# GPIOPins.net
KiCad netlist of a schematic drawn in Altium Designer
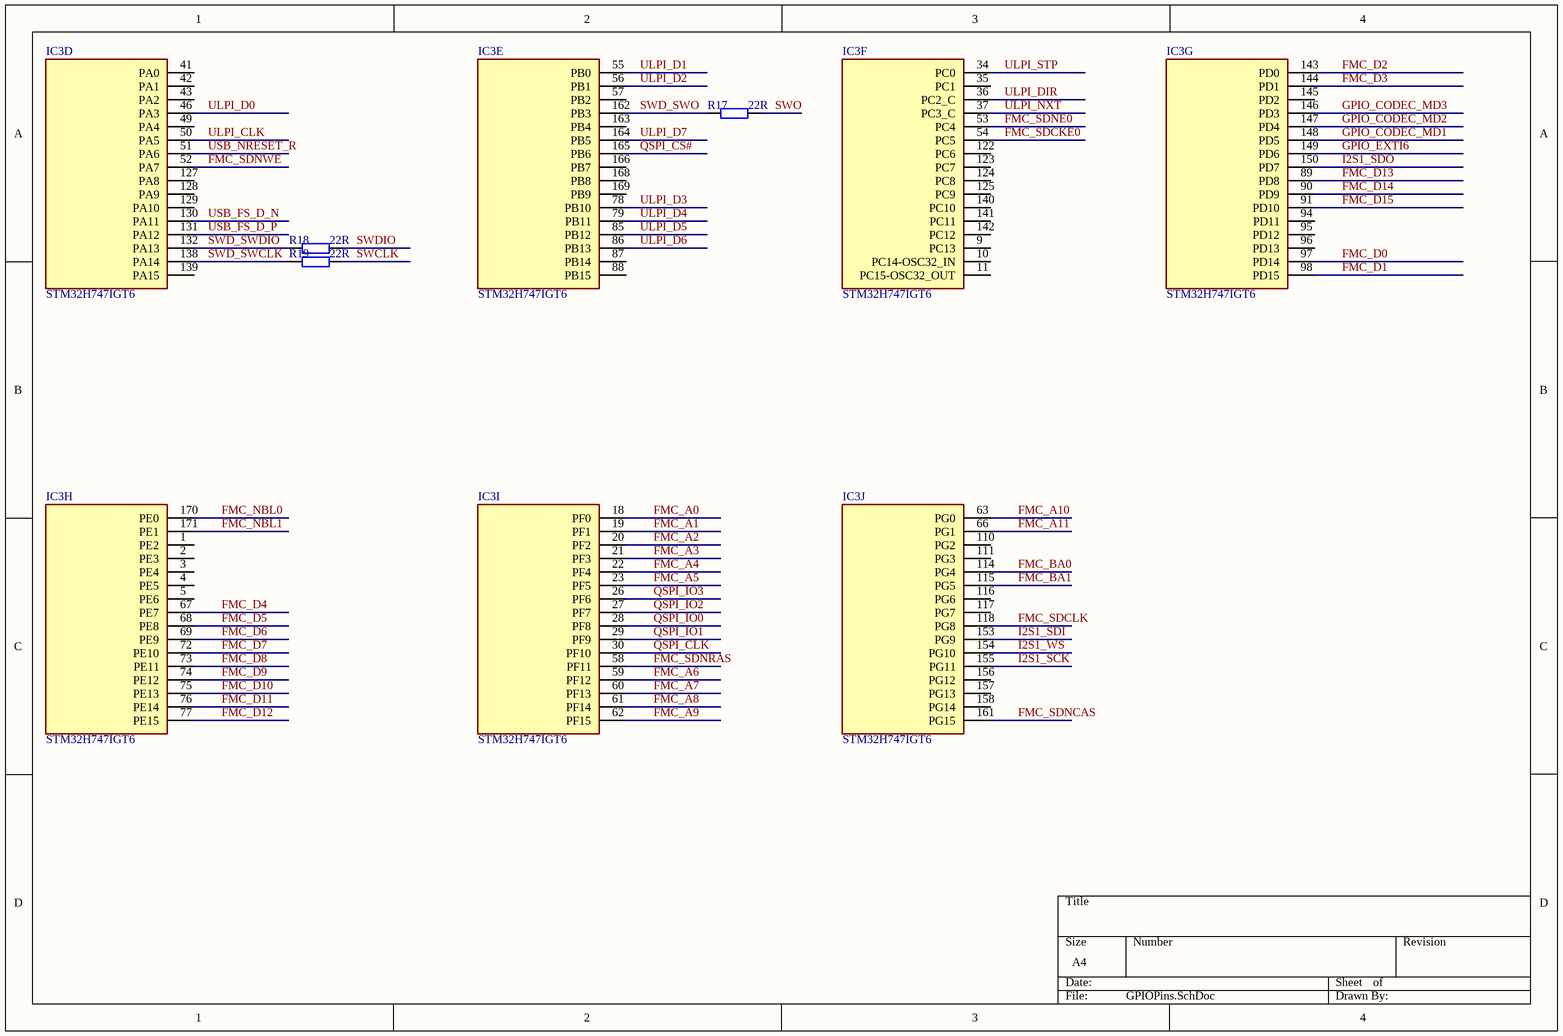
[diagram p0: GPIOPins.SchDoc]

(export (version "E")
  (design (tool "Eeschema 10.0.6"))
  (components
    (comp (ref "IC3")
      (value "STM32H747IGT6")
      (footprint "Footprint-Lib-PhilsLab:QFP50P2600X2600X160-176N")
      (description "Integrated Circuit")
      (fields (field (name "MOUSER PART NUMBER") "511-STM32H747IGT6"))
      (libsource (lib "Schematic-Lib-PhilsLab") (part "STM32H747IGT6"))
    )
    (comp (ref "R17")
      (value "22R")
      (footprint "RES_0402")
      (description "Resistor SMD 0402")
      (libsource (lib "Schematic-Lib-PhilsLab") (part "RES_0402"))
    )
    (comp (ref "R18")
      (value "22R")
      (footprint "RES_0402")
      (description "Resistor SMD 0402")
      (libsource (lib "Schematic-Lib-PhilsLab") (part "RES_0402"))
    )
    (comp (ref "R19")
      (value "22R")
      (footprint "RES_0402")
      (description "Resistor SMD 0402")
      (libsource (lib "Schematic-Lib-PhilsLab") (part "RES_0402"))
    )
  )
  (nets
    (net (code "1") (name "/FMC_A0") (class "Default")
      (node (ref "IC3") (pin "18") (pinfunction "PF0_18") (pintype "passive"))
    )
    (net (code "2") (name "/FMC_A1") (class "Default")
      (node (ref "IC3") (pin "19") (pinfunction "PF1_19") (pintype "passive"))
    )
    (net (code "3") (name "/FMC_A2") (class "Default")
      (node (ref "IC3") (pin "20") (pinfunction "PF2_20") (pintype "passive"))
    )
    (net (code "4") (name "/FMC_A3") (class "Default")
      (node (ref "IC3") (pin "21") (pinfunction "PF3_21") (pintype "passive"))
    )
    (net (code "5") (name "/FMC_A4") (class "Default")
      (node (ref "IC3") (pin "22") (pinfunction "PF4_22") (pintype "passive"))
    )
    (net (code "6") (name "/FMC_A5") (class "Default")
      (node (ref "IC3") (pin "23") (pinfunction "PF5_23") (pintype "passive"))
    )
    (net (code "7") (name "/FMC_A6") (class "Default")
      (node (ref "IC3") (pin "59") (pinfunction "PF12_59") (pintype "passive"))
    )
    (net (code "8") (name "/FMC_A7") (class "Default")
      (node (ref "IC3") (pin "60") (pinfunction "PF13_60") (pintype "passive"))
    )
    (net (code "9") (name "/FMC_A8") (class "Default")
      (node (ref "IC3") (pin "61") (pinfunction "PF14_61") (pintype "passive"))
    )
    (net (code "10") (name "/FMC_A9") (class "Default")
      (node (ref "IC3") (pin "62") (pinfunction "PF15_62") (pintype "passive"))
    )
    (net (code "11") (name "/FMC_A10") (class "Default")
      (node (ref "IC3") (pin "63") (pinfunction "PG0_63") (pintype "passive"))
    )
    (net (code "12") (name "/FMC_A11") (class "Default")
      (node (ref "IC3") (pin "66") (pinfunction "PG1_66") (pintype "passive"))
    )
    (net (code "13") (name "/FMC_BA0") (class "Default")
      (node (ref "IC3") (pin "114") (pinfunction "PG4_114") (pintype "passive"))
    )
    (net (code "14") (name "/FMC_BA1") (class "Default")
      (node (ref "IC3") (pin "115") (pinfunction "PG5_115") (pintype "passive"))
    )
    (net (code "15") (name "/FMC_D0") (class "Default")
      (node (ref "IC3") (pin "97") (pinfunction "PD14_97") (pintype "passive"))
    )
    (net (code "16") (name "/FMC_D1") (class "Default")
      (node (ref "IC3") (pin "98") (pinfunction "PD15_98") (pintype "passive"))
    )
    (net (code "17") (name "/FMC_D2") (class "Default")
      (node (ref "IC3") (pin "143") (pinfunction "PD0_143") (pintype "passive"))
    )
    (net (code "18") (name "/FMC_D3") (class "Default")
      (node (ref "IC3") (pin "144") (pinfunction "PD1_144") (pintype "passive"))
    )
    (net (code "19") (name "/FMC_D4") (class "Default")
      (node (ref "IC3") (pin "67") (pinfunction "PE7_67") (pintype "passive"))
    )
    (net (code "20") (name "/FMC_D5") (class "Default")
      (node (ref "IC3") (pin "68") (pinfunction "PE8_68") (pintype "passive"))
    )
    (net (code "21") (name "/FMC_D6") (class "Default")
      (node (ref "IC3") (pin "69") (pinfunction "PE9_69") (pintype "passive"))
    )
    (net (code "22") (name "/FMC_D7") (class "Default")
      (node (ref "IC3") (pin "72") (pinfunction "PE10_72") (pintype "passive"))
    )
    (net (code "23") (name "/FMC_D8") (class "Default")
      (node (ref "IC3") (pin "73") (pinfunction "PE11_73") (pintype "passive"))
    )
    (net (code "24") (name "/FMC_D9") (class "Default")
      (node (ref "IC3") (pin "74") (pinfunction "PE12_74") (pintype "passive"))
    )
    (net (code "25") (name "/FMC_D10") (class "Default")
      (node (ref "IC3") (pin "75") (pinfunction "PE13_75") (pintype "passive"))
    )
    (net (code "26") (name "/FMC_D11") (class "Default")
      (node (ref "IC3") (pin "76") (pinfunction "PE14_76") (pintype "passive"))
    )
    (net (code "27") (name "/FMC_D12") (class "Default")
      (node (ref "IC3") (pin "77") (pinfunction "PE15_77") (pintype "passive"))
    )
    (net (code "28") (name "/FMC_D13") (class "Default")
      (node (ref "IC3") (pin "89") (pinfunction "PD8_89") (pintype "passive"))
    )
    (net (code "29") (name "/FMC_D14") (class "Default")
      (node (ref "IC3") (pin "90") (pinfunction "PD9_90") (pintype "passive"))
    )
    (net (code "30") (name "/FMC_D15") (class "Default")
      (node (ref "IC3") (pin "91") (pinfunction "PD10_91") (pintype "passive"))
    )
    (net (code "31") (name "/FMC_NBL0") (class "Default")
      (node (ref "IC3") (pin "170") (pinfunction "PE0_170") (pintype "passive"))
    )
    (net (code "32") (name "/FMC_NBL1") (class "Default")
      (node (ref "IC3") (pin "171") (pinfunction "PE1_171") (pintype "passive"))
    )
    (net (code "33") (name "/FMC_SDCKE0") (class "Default")
      (node (ref "IC3") (pin "54") (pinfunction "PC5_54") (pintype "passive"))
    )
    (net (code "34") (name "/FMC_SDCLK") (class "Default")
      (node (ref "IC3") (pin "118") (pinfunction "PG8_118") (pintype "passive"))
    )
    (net (code "35") (name "/FMC_SDNCAS") (class "Default")
      (node (ref "IC3") (pin "161") (pinfunction "PG15_161") (pintype "passive"))
    )
    (net (code "36") (name "/FMC_SDNE0") (class "Default")
      (node (ref "IC3") (pin "53") (pinfunction "PC4_53") (pintype "passive"))
    )
    (net (code "37") (name "/FMC_SDNRAS") (class "Default")
      (node (ref "IC3") (pin "58") (pinfunction "PF11_58") (pintype "passive"))
    )
    (net (code "38") (name "/FMC_SDNWE") (class "Default")
      (node (ref "IC3") (pin "52") (pinfunction "PA7_52") (pintype "passive"))
    )
    (net (code "39") (name "/GPIO_CODEC_MD1") (class "Default")
      (node (ref "IC3") (pin "148") (pinfunction "PD5_148") (pintype "passive"))
    )
    (net (code "40") (name "/GPIO_CODEC_MD2") (class "Default")
      (node (ref "IC3") (pin "147") (pinfunction "PD4_147") (pintype "passive"))
    )
    (net (code "41") (name "/GPIO_CODEC_MD3") (class "Default")
      (node (ref "IC3") (pin "146") (pinfunction "PD3_146") (pintype "passive"))
    )
    (net (code "42") (name "/GPIO_EXTI6") (class "Default")
      (node (ref "IC3") (pin "149") (pinfunction "PD6_149") (pintype "passive"))
    )
    (net (code "43") (name "/I2S1_SCK") (class "Default")
      (node (ref "IC3") (pin "155") (pinfunction "PG11_155") (pintype "passive"))
    )
    (net (code "44") (name "/I2S1_SDI") (class "Default")
      (node (ref "IC3") (pin "153") (pinfunction "PG9_153") (pintype "passive"))
    )
    (net (code "45") (name "/I2S1_SDO") (class "Default")
      (node (ref "IC3") (pin "150") (pinfunction "PD7_150") (pintype "passive"))
    )
    (net (code "46") (name "/I2S1_WS") (class "Default")
      (node (ref "IC3") (pin "154") (pinfunction "PG10_154") (pintype "passive"))
    )
    (net (code "47") (name "/QSPI_CLK") (class "Default")
      (node (ref "IC3") (pin "30") (pinfunction "PF10_30") (pintype "passive"))
    )
    (net (code "48") (name "/QSPI_CS#") (class "Default")
      (node (ref "IC3") (pin "165") (pinfunction "PB6_165") (pintype "passive"))
    )
    (net (code "49") (name "/QSPI_IO0") (class "Default")
      (node (ref "IC3") (pin "28") (pinfunction "PF8_28") (pintype "passive"))
    )
    (net (code "50") (name "/QSPI_IO1") (class "Default")
      (node (ref "IC3") (pin "29") (pinfunction "PF9_29") (pintype "passive"))
    )
    (net (code "51") (name "/QSPI_IO2") (class "Default")
      (node (ref "IC3") (pin "27") (pinfunction "PF7_27") (pintype "passive"))
    )
    (net (code "52") (name "/QSPI_IO3") (class "Default")
      (node (ref "IC3") (pin "26") (pinfunction "PF6_26") (pintype "passive"))
    )
    (net (code "53") (name "/SWCLK") (class "Default")
      (node (ref "R19") (pin "1") (pinfunction "1_1") (pintype "passive"))
    )
    (net (code "54") (name "/SWDIO") (class "Default")
      (node (ref "R18") (pin "1") (pinfunction "1_1") (pintype "passive"))
    )
    (net (code "55") (name "/SWD_SWCLK") (class "Default")
      (node (ref "IC3") (pin "138") (pinfunction "PA14_138") (pintype "passive"))
      (node (ref "R19") (pin "2") (pinfunction "2_2") (pintype "passive"))
    )
    (net (code "56") (name "/SWD_SWDIO") (class "Default")
      (node (ref "IC3") (pin "132") (pinfunction "PA13_132") (pintype "passive"))
      (node (ref "R18") (pin "2") (pinfunction "2_2") (pintype "passive"))
    )
    (net (code "57") (name "/SWD_SWO") (class "Default")
      (node (ref "IC3") (pin "162") (pinfunction "PB3_162") (pintype "passive"))
      (node (ref "R17") (pin "2") (pinfunction "2_2") (pintype "passive"))
    )
    (net (code "58") (name "/SWO") (class "Default")
      (node (ref "R17") (pin "1") (pinfunction "1_1") (pintype "passive"))
    )
    (net (code "59") (name "/ULPI_CLK") (class "Default")
      (node (ref "IC3") (pin "50") (pinfunction "PA5_50") (pintype "passive"))
    )
    (net (code "60") (name "/ULPI_D0") (class "Default")
      (node (ref "IC3") (pin "46") (pinfunction "PA3_46") (pintype "passive"))
    )
    (net (code "61") (name "/ULPI_D1") (class "Default")
      (node (ref "IC3") (pin "55") (pinfunction "PB0_55") (pintype "passive"))
    )
    (net (code "62") (name "/ULPI_D2") (class "Default")
      (node (ref "IC3") (pin "56") (pinfunction "PB1_56") (pintype "passive"))
    )
    (net (code "63") (name "/ULPI_D3") (class "Default")
      (node (ref "IC3") (pin "78") (pinfunction "PB10_78") (pintype "passive"))
    )
    (net (code "64") (name "/ULPI_D4") (class "Default")
      (node (ref "IC3") (pin "79") (pinfunction "PB11_79") (pintype "passive"))
    )
    (net (code "65") (name "/ULPI_D5") (class "Default")
      (node (ref "IC3") (pin "85") (pinfunction "PB12_85") (pintype "passive"))
    )
    (net (code "66") (name "/ULPI_D6") (class "Default")
      (node (ref "IC3") (pin "86") (pinfunction "PB13_86") (pintype "passive"))
    )
    (net (code "67") (name "/ULPI_D7") (class "Default")
      (node (ref "IC3") (pin "164") (pinfunction "PB5_164") (pintype "passive"))
    )
    (net (code "68") (name "/ULPI_DIR") (class "Default")
      (node (ref "IC3") (pin "36") (pinfunction "PC2_C_36") (pintype "passive"))
    )
    (net (code "69") (name "/ULPI_NXT") (class "Default")
      (node (ref "IC3") (pin "37") (pinfunction "PC3_C_37") (pintype "passive"))
    )
    (net (code "70") (name "/ULPI_STP") (class "Default")
      (node (ref "IC3") (pin "34") (pinfunction "PC0_34") (pintype "passive"))
    )
    (net (code "71") (name "/USB_FS_D_N") (class "Default")
      (node (ref "IC3") (pin "130") (pinfunction "PA11_130") (pintype "passive"))
    )
    (net (code "72") (name "/USB_FS_D_P") (class "Default")
      (node (ref "IC3") (pin "131") (pinfunction "PA12_131") (pintype "passive"))
    )
    (net (code "73") (name "/USB_NRESET_R") (class "Default")
      (node (ref "IC3") (pin "51") (pinfunction "PA6_51") (pintype "passive"))
    )
    (net (code "74") (name "unconnected-(IC3D-PA0-Pad41)") (class "Default")
      (node (ref "IC3") (pin "41") (pinfunction "PA0_41") (pintype "passive"))
    )
    (net (code "75") (name "unconnected-(IC3D-PA1-Pad42)") (class "Default")
      (node (ref "IC3") (pin "42") (pinfunction "PA1_42") (pintype "passive"))
    )
    (net (code "76") (name "unconnected-(IC3D-PA2-Pad43)") (class "Default")
      (node (ref "IC3") (pin "43") (pinfunction "PA2_43") (pintype "passive"))
    )
    (net (code "77") (name "unconnected-(IC3D-PA4-Pad49)") (class "Default")
      (node (ref "IC3") (pin "49") (pinfunction "PA4_49") (pintype "passive"))
    )
    (net (code "78") (name "unconnected-(IC3D-PA8-Pad127)") (class "Default")
      (node (ref "IC3") (pin "127") (pinfunction "PA8_127") (pintype "passive"))
    )
    (net (code "79") (name "unconnected-(IC3D-PA9-Pad128)") (class "Default")
      (node (ref "IC3") (pin "128") (pinfunction "PA9_128") (pintype "passive"))
    )
    (net (code "80") (name "unconnected-(IC3D-PA10-Pad129)") (class "Default")
      (node (ref "IC3") (pin "129") (pinfunction "PA10_129") (pintype "passive"))
    )
    (net (code "81") (name "unconnected-(IC3D-PA15-Pad139)") (class "Default")
      (node (ref "IC3") (pin "139") (pinfunction "PA15_139") (pintype "passive"))
    )
    (net (code "82") (name "unconnected-(IC3E-PB2-Pad57)") (class "Default")
      (node (ref "IC3") (pin "57") (pinfunction "PB2_57") (pintype "passive"))
    )
    (net (code "83") (name "unconnected-(IC3E-PB4-Pad163)") (class "Default")
      (node (ref "IC3") (pin "163") (pinfunction "PB4_163") (pintype "passive"))
    )
    (net (code "84") (name "unconnected-(IC3E-PB7-Pad166)") (class "Default")
      (node (ref "IC3") (pin "166") (pinfunction "PB7_166") (pintype "passive"))
    )
    (net (code "85") (name "unconnected-(IC3E-PB8-Pad168)") (class "Default")
      (node (ref "IC3") (pin "168") (pinfunction "PB8_168") (pintype "passive"))
    )
    (net (code "86") (name "unconnected-(IC3E-PB9-Pad169)") (class "Default")
      (node (ref "IC3") (pin "169") (pinfunction "PB9_169") (pintype "passive"))
    )
    (net (code "87") (name "unconnected-(IC3E-PB14-Pad87)") (class "Default")
      (node (ref "IC3") (pin "87") (pinfunction "PB14_87") (pintype "passive"))
    )
    (net (code "88") (name "unconnected-(IC3E-PB15-Pad88)") (class "Default")
      (node (ref "IC3") (pin "88") (pinfunction "PB15_88") (pintype "passive"))
    )
    (net (code "89") (name "unconnected-(IC3F-PC1-Pad35)") (class "Default")
      (node (ref "IC3") (pin "35") (pinfunction "PC1_35") (pintype "passive"))
    )
    (net (code "90") (name "unconnected-(IC3F-PC6-Pad122)") (class "Default")
      (node (ref "IC3") (pin "122") (pinfunction "PC6_122") (pintype "passive"))
    )
    (net (code "91") (name "unconnected-(IC3F-PC7-Pad123)") (class "Default")
      (node (ref "IC3") (pin "123") (pinfunction "PC7_123") (pintype "passive"))
    )
    (net (code "92") (name "unconnected-(IC3F-PC8-Pad124)") (class "Default")
      (node (ref "IC3") (pin "124") (pinfunction "PC8_124") (pintype "passive"))
    )
    (net (code "93") (name "unconnected-(IC3F-PC9-Pad125)") (class "Default")
      (node (ref "IC3") (pin "125") (pinfunction "PC9_125") (pintype "passive"))
    )
    (net (code "94") (name "unconnected-(IC3F-PC10-Pad140)") (class "Default")
      (node (ref "IC3") (pin "140") (pinfunction "PC10_140") (pintype "passive"))
    )
    (net (code "95") (name "unconnected-(IC3F-PC11-Pad141)") (class "Default")
      (node (ref "IC3") (pin "141") (pinfunction "PC11_141") (pintype "passive"))
    )
    (net (code "96") (name "unconnected-(IC3F-PC12-Pad142)") (class "Default")
      (node (ref "IC3") (pin "142") (pinfunction "PC12_142") (pintype "passive"))
    )
    (net (code "97") (name "unconnected-(IC3F-PC13-Pad9)") (class "Default")
      (node (ref "IC3") (pin "9") (pinfunction "PC13_9") (pintype "passive"))
    )
    (net (code "98") (name "unconnected-(IC3F-PC14-OSC32_IN-Pad10)") (class "Default")
      (node (ref "IC3") (pin "10") (pinfunction "PC14-OSC32_IN_10") (pintype "passive"))
    )
    (net (code "99") (name "unconnected-(IC3F-PC15-OSC32_OUT-Pad11)") (class "Default")
      (node (ref "IC3") (pin "11") (pinfunction "PC15-OSC32_OUT_11") (pintype "passive"))
    )
    (net (code "100") (name "unconnected-(IC3G-PD2-Pad145)") (class "Default")
      (node (ref "IC3") (pin "145") (pinfunction "PD2_145") (pintype "passive"))
    )
    (net (code "101") (name "unconnected-(IC3G-PD11-Pad94)") (class "Default")
      (node (ref "IC3") (pin "94") (pinfunction "PD11_94") (pintype "passive"))
    )
    (net (code "102") (name "unconnected-(IC3G-PD12-Pad95)") (class "Default")
      (node (ref "IC3") (pin "95") (pinfunction "PD12_95") (pintype "passive"))
    )
    (net (code "103") (name "unconnected-(IC3G-PD13-Pad96)") (class "Default")
      (node (ref "IC3") (pin "96") (pinfunction "PD13_96") (pintype "passive"))
    )
    (net (code "104") (name "unconnected-(IC3H-PE2-Pad1)") (class "Default")
      (node (ref "IC3") (pin "1") (pinfunction "PE2_1") (pintype "passive"))
    )
    (net (code "105") (name "unconnected-(IC3H-PE3-Pad2)") (class "Default")
      (node (ref "IC3") (pin "2") (pinfunction "PE3_2") (pintype "passive"))
    )
    (net (code "106") (name "unconnected-(IC3H-PE4-Pad3)") (class "Default")
      (node (ref "IC3") (pin "3") (pinfunction "PE4_3") (pintype "passive"))
    )
    (net (code "107") (name "unconnected-(IC3H-PE5-Pad4)") (class "Default")
      (node (ref "IC3") (pin "4") (pinfunction "PE5_4") (pintype "passive"))
    )
    (net (code "108") (name "unconnected-(IC3H-PE6-Pad5)") (class "Default")
      (node (ref "IC3") (pin "5") (pinfunction "PE6_5") (pintype "passive"))
    )
    (net (code "109") (name "unconnected-(IC3J-PG2-Pad110)") (class "Default")
      (node (ref "IC3") (pin "110") (pinfunction "PG2_110") (pintype "passive"))
    )
    (net (code "110") (name "unconnected-(IC3J-PG3-Pad111)") (class "Default")
      (node (ref "IC3") (pin "111") (pinfunction "PG3_111") (pintype "passive"))
    )
    (net (code "111") (name "unconnected-(IC3J-PG6-Pad116)") (class "Default")
      (node (ref "IC3") (pin "116") (pinfunction "PG6_116") (pintype "passive"))
    )
    (net (code "112") (name "unconnected-(IC3J-PG7-Pad117)") (class "Default")
      (node (ref "IC3") (pin "117") (pinfunction "PG7_117") (pintype "passive"))
    )
    (net (code "113") (name "unconnected-(IC3J-PG12-Pad156)") (class "Default")
      (node (ref "IC3") (pin "156") (pinfunction "PG12_156") (pintype "passive"))
    )
    (net (code "114") (name "unconnected-(IC3J-PG13-Pad157)") (class "Default")
      (node (ref "IC3") (pin "157") (pinfunction "PG13_157") (pintype "passive"))
    )
    (net (code "115") (name "unconnected-(IC3J-PG14-Pad158)") (class "Default")
      (node (ref "IC3") (pin "158") (pinfunction "PG14_158") (pintype "passive"))
    )
  )
)
